# RasPiHAT-SOUND.net
KiCad netlist of a schematic drawn in Altium Designer
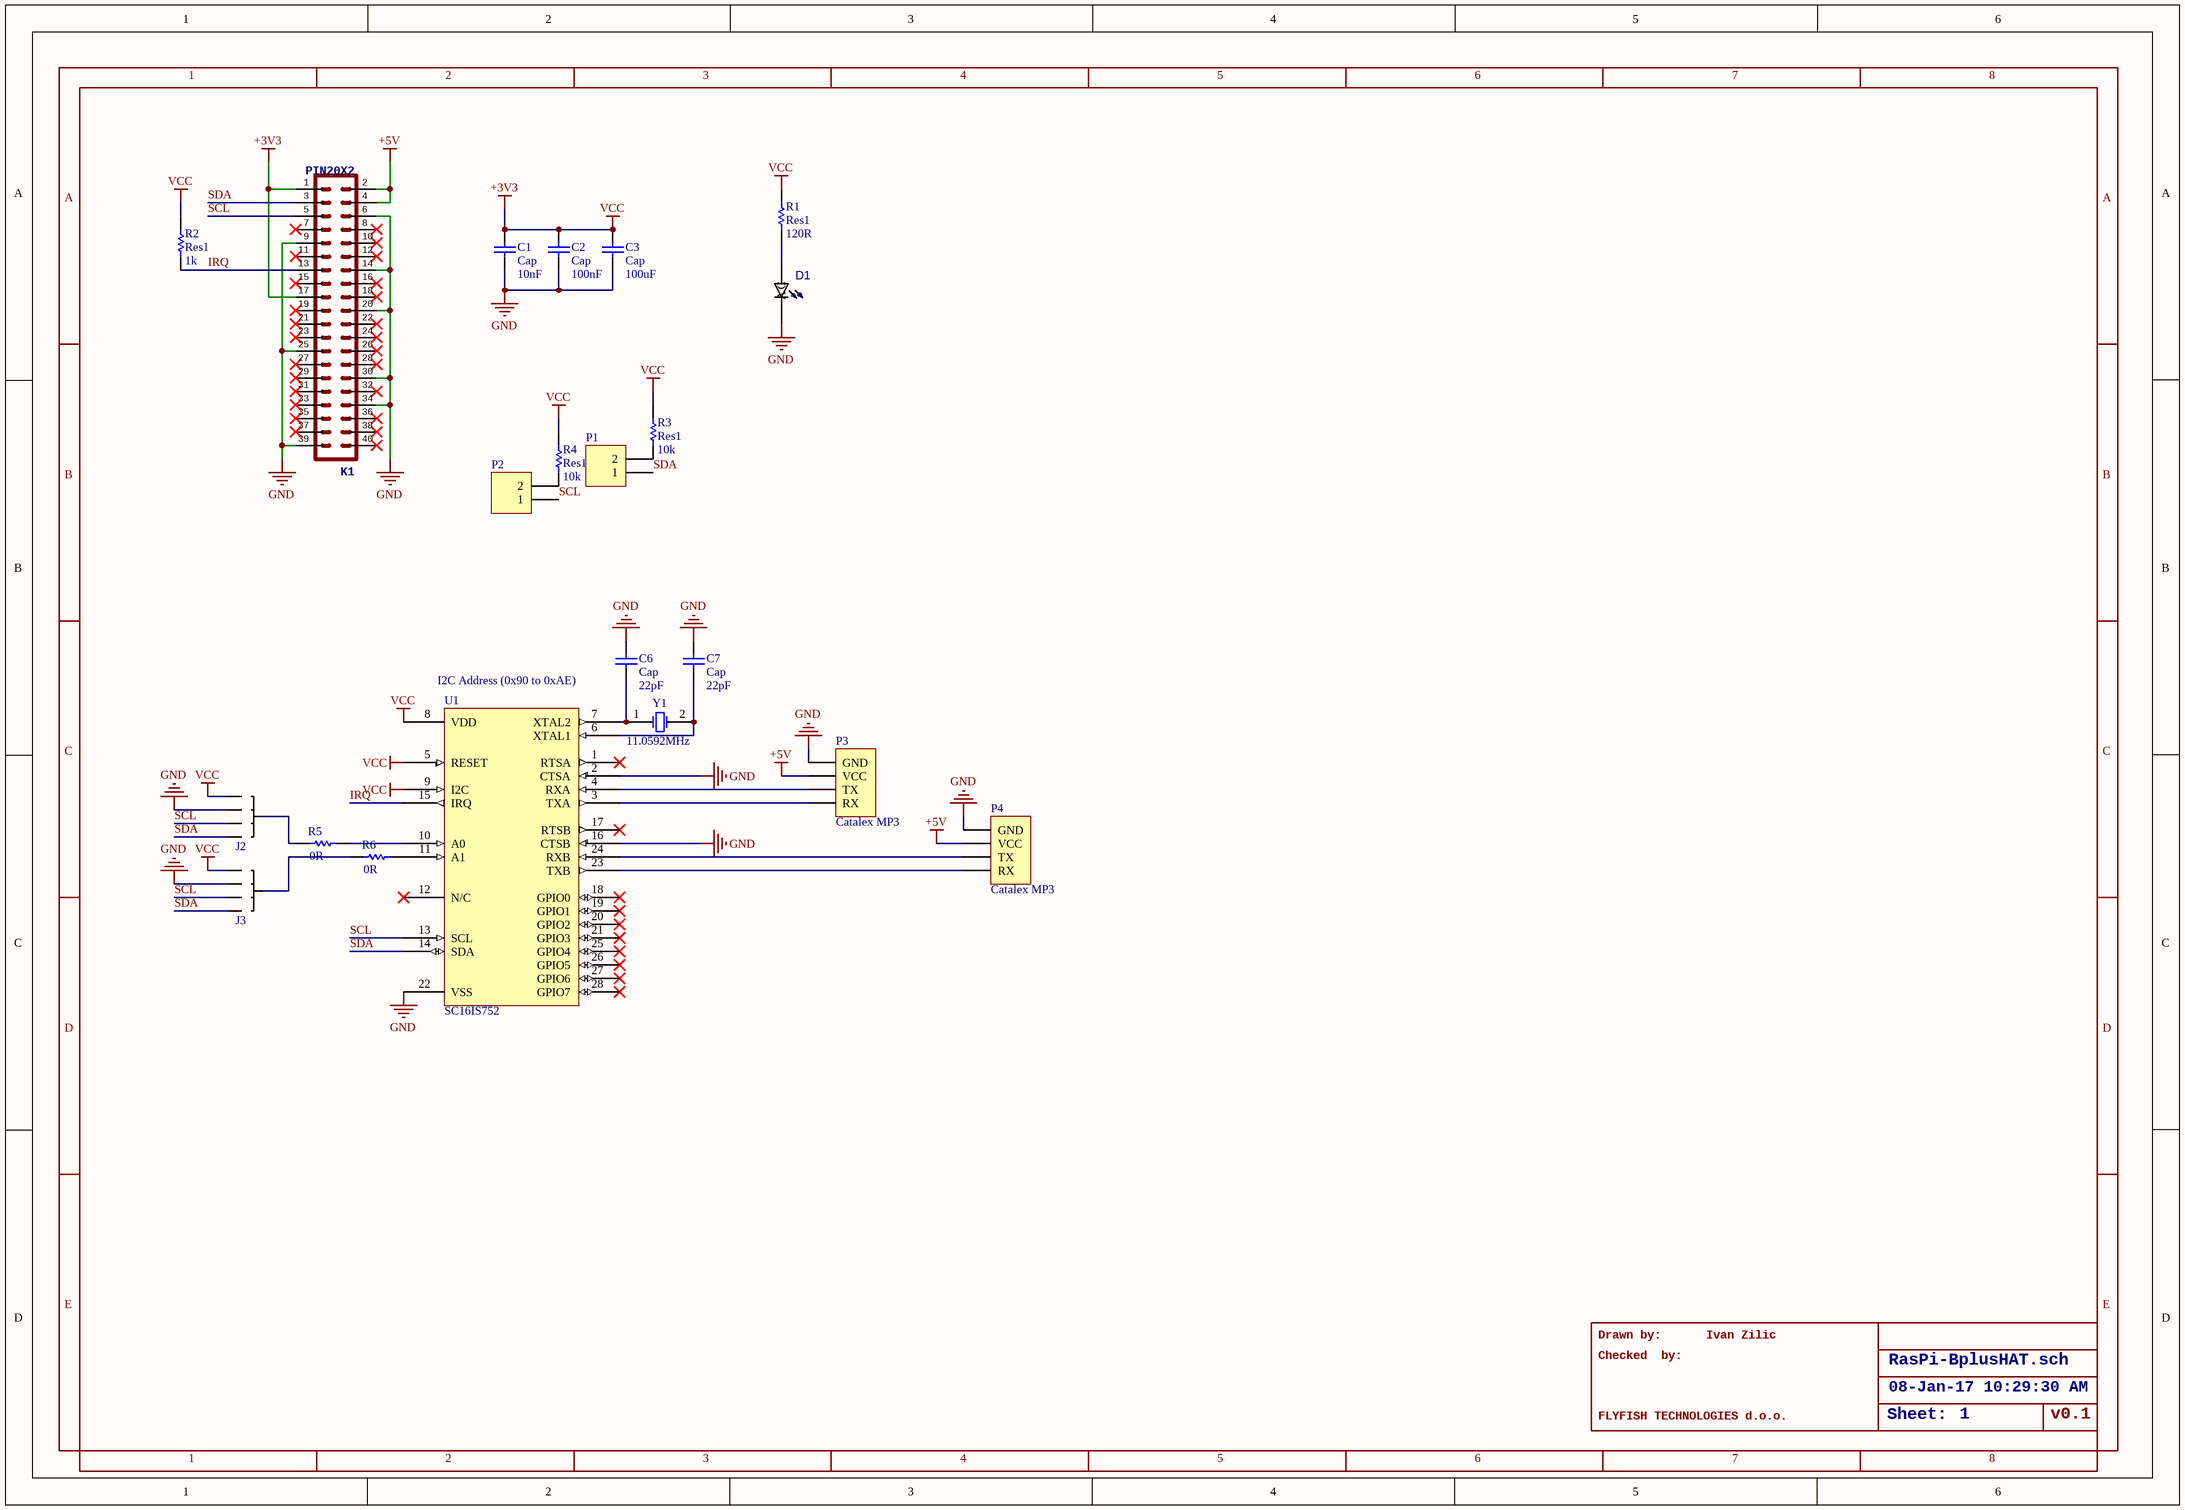
[diagram p0: RasPiHAT-SOUND.SchDoc]

(export (version "E")
  (design (tool "Eeschema 10.0.6"))
  (components
    (comp (ref "C1")
      (value "Cap")
      (footprint "6-0805_N")
      (description "Capacitor")
      (fields (field (name "ALTIUM_VALUE") "10nF") (field (name "PUBLISHER") "Altium Limited"))
      (libsource (lib "Miscellaneous Devices") (part "Cap"))
    )
    (comp (ref "C2")
      (value "Cap")
      (footprint "6-0805_N")
      (description "Capacitor")
      (fields (field (name "ALTIUM_VALUE") "100nF") (field (name "PUBLISHER") "Altium Limited"))
      (libsource (lib "Miscellaneous Devices") (part "Cap"))
    )
    (comp (ref "C3")
      (value "Cap")
      (footprint "6-0805_N")
      (description "Capacitor")
      (fields (field (name "ALTIUM_VALUE") "100uF") (field (name "PUBLISHER") "Altium Limited"))
      (libsource (lib "Miscellaneous Devices") (part "Cap"))
    )
    (comp (ref "C6")
      (value "Cap")
      (footprint "6-0805_N")
      (description "Capacitor")
      (fields (field (name "ALTIUM_VALUE") "22pF") (field (name "PUBLISHER") "Altium Limited"))
      (libsource (lib "Miscellaneous Devices") (part "Cap"))
    )
    (comp (ref "C7")
      (value "Cap")
      (footprint "6-0805_N")
      (description "Capacitor")
      (fields (field (name "ALTIUM_VALUE") "22pF") (field (name "PUBLISHER") "Altium Limited"))
      (libsource (lib "Miscellaneous Devices") (part "Cap"))
    )
    (comp (ref "D1")
      (value "0805_LED")
      (footprint "LEDSC200X125X70-2N_598-8160-107F(Primary)")
      (description "LED, SMD; 0805; Yellow-Green; Water Clear Lens; 40mcd; 570/575nm")
      (fields (field (name "MP") "598-8160-107F") (field (name "MF") "Dialight"))
      (libsource (lib "0805_LED") (part "598-8160-107F"))
    )
    (comp (ref "J2")
      (value "Shortable Link (4 Way)")
      (footprint "ShortableLink(4Way)")
      (libsource (lib "ShortableLink") (part "Shortable Link (4 Way)"))
    )
    (comp (ref "J3")
      (value "Shortable Link (4 Way)")
      (footprint "ShortableLink(4Way)")
      (libsource (lib "ShortableLink") (part "Shortable Link (4 Way)"))
    )
    (comp (ref "K1")
      (value "PIN20X2")
      (footprint "HDR2X20")
      (fields (field (name ">VALUE") "PIN20X2") (field (name ">NAME") "K1"))
      (libsource (lib "FLYFISH") (part "PIN20X2"))
    )
    (comp (ref "P1")
      (value "Header 2")
      (footprint "HDR1X2")
      (description "Header, 2-Pin")
      (fields (field (name "PUBLISHER") "Altium Limited"))
      (libsource (lib "Miscellaneous Connectors") (part "Header 2"))
    )
    (comp (ref "P2")
      (value "Header 2")
      (footprint "HDR1X2")
      (description "Header, 2-Pin")
      (fields (field (name "PUBLISHER") "Altium Limited"))
      (libsource (lib "Miscellaneous Connectors") (part "Header 2"))
    )
    (comp (ref "P3")
      (value "Catalex MP3")
      (footprint "YX5300_UART")
      (description "Header, 4-Pin")
      (fields (field (name "PUBLISHER") "Altium Limited"))
      (libsource (lib "Miscellaneous Connectors") (part "Header 4"))
    )
    (comp (ref "P4")
      (value "Catalex MP3")
      (footprint "YX5300_UART")
      (description "Header, 4-Pin")
      (fields (field (name "PUBLISHER") "Altium Limited"))
      (libsource (lib "Miscellaneous Connectors") (part "Header 4"))
    )
    (comp (ref "R1")
      (value "Res1")
      (footprint "6-0805_N")
      (description "Resistor")
      (fields (field (name "ALTIUM_VALUE") "120R") (field (name "PUBLISHER") "Altium Limited"))
      (libsource (lib "Miscellaneous Devices") (part "Res1"))
    )
    (comp (ref "R2")
      (value "Res1")
      (footprint "6-0805_N")
      (description "Resistor")
      (fields (field (name "ALTIUM_VALUE") "1k") (field (name "PUBLISHER") "Altium Limited"))
      (libsource (lib "Miscellaneous Devices") (part "Res1"))
    )
    (comp (ref "R3")
      (value "Res1")
      (footprint "6-0805_N")
      (description "Resistor")
      (fields (field (name "ALTIUM_VALUE") "10k") (field (name "PUBLISHER") "Altium Limited"))
      (libsource (lib "Miscellaneous Devices") (part "Res1"))
    )
    (comp (ref "R4")
      (value "Res1")
      (footprint "6-0805_N")
      (description "Resistor")
      (fields (field (name "ALTIUM_VALUE") "10k") (field (name "PUBLISHER") "Altium Limited"))
      (libsource (lib "Miscellaneous Devices") (part "Res1"))
    )
    (comp (ref "R5")
      (value "0R")
      (footprint "6-0805_N")
      (description "Resistor")
      (fields (field (name "Comment") "Res1") (field (name "PUBLISHER") "Altium Limited"))
      (libsource (lib "Miscellaneous Devices") (part "Res1"))
    )
    (comp (ref "R6")
      (value "0R")
      (footprint "6-0805_N")
      (description "Resistor")
      (fields (field (name "Comment") "Res1") (field (name "PUBLISHER") "Altium Limited"))
      (libsource (lib "Miscellaneous Devices") (part "Res1"))
    )
    (comp (ref "U1")
      (value "SC16IS752")
      (description "I2C to UART Interface (2 Channels)")
      (libsource (lib "NXP_UART_Interfaces") (part "SC16IS752IPW"))
    )
    (comp (ref "Y1")
      (value "11.0592MHz")
      (footprint "Crystals:SMD Crystal")
      (description "Crystal Oscillator")
      (fields (field (name "PUBLISHER") "Altium Limited"))
      (libsource (lib "Miscellaneous Devices") (part "XTAL"))
    )
  )
  (nets
    (net (code "1") (name "+3V3") (class "Default")
      (node (ref "C1") (pin "2") (pinfunction "2_2") (pintype "passive"))
      (node (ref "C2") (pin "2") (pinfunction "2_2") (pintype "passive"))
      (node (ref "C3") (pin "2") (pinfunction "2_2") (pintype "passive"))
      (node (ref "J2") (pin "5") (pinfunction "5_5") (pintype "passive"))
      (node (ref "J3") (pin "5") (pinfunction "5_5") (pintype "passive"))
      (node (ref "K1") (pin "1") (pinfunction "1_1") (pintype "passive"))
      (node (ref "K1") (pin "17") (pinfunction "17_17") (pintype "passive"))
      (node (ref "R1") (pin "1") (pinfunction "1_1") (pintype "passive"))
      (node (ref "R2") (pin "1") (pinfunction "1_1") (pintype "passive"))
      (node (ref "R3") (pin "1") (pinfunction "1_1") (pintype "passive"))
      (node (ref "R4") (pin "1") (pinfunction "1_1") (pintype "passive"))
      (node (ref "U1") (pin "5") (pinfunction "RESET_5") (pintype "input"))
      (node (ref "U1") (pin "8") (pinfunction "VDD_8") (pintype "passive"))
      (node (ref "U1") (pin "9") (pinfunction "I2C_9") (pintype "input"))
    )
    (net (code "2") (name "+5V") (class "Default")
      (node (ref "K1") (pin "2") (pinfunction "2_2") (pintype "passive"))
      (node (ref "K1") (pin "4") (pinfunction "4_4") (pintype "passive"))
      (node (ref "P3") (pin "2") (pinfunction "VCC_2") (pintype "passive"))
      (node (ref "P4") (pin "2") (pinfunction "VCC_2") (pintype "passive"))
    )
    (net (code "3") (name "/IRQ") (class "Default")
      (node (ref "K1") (pin "13") (pinfunction "13_13") (pintype "passive"))
      (node (ref "R2") (pin "2") (pinfunction "2_2") (pintype "passive"))
      (node (ref "U1") (pin "15") (pinfunction "IRQ_15") (pintype "output"))
    )
    (net (code "4") (name "/SCL") (class "Default")
      (node (ref "J2") (pin "3") (pinfunction "3_3") (pintype "passive"))
      (node (ref "J3") (pin "3") (pinfunction "3_3") (pintype "passive"))
      (node (ref "K1") (pin "5") (pinfunction "5_5") (pintype "passive"))
      (node (ref "P2") (pin "1") (pinfunction "1_1") (pintype "passive"))
      (node (ref "U1") (pin "13") (pinfunction "SCL_13") (pintype "input"))
    )
    (net (code "5") (name "/SDA") (class "Default")
      (node (ref "J2") (pin "2") (pinfunction "2_2") (pintype "passive"))
      (node (ref "J3") (pin "2") (pinfunction "2_2") (pintype "passive"))
      (node (ref "K1") (pin "3") (pinfunction "3_3") (pintype "passive"))
      (node (ref "P1") (pin "1") (pinfunction "1_1") (pintype "passive"))
      (node (ref "U1") (pin "14") (pinfunction "SDA_14") (pintype "bidirectional"))
    )
    (net (code "6") (name "GND") (class "Default")
      (node (ref "C1") (pin "1") (pinfunction "1_1") (pintype "passive"))
      (node (ref "C2") (pin "1") (pinfunction "1_1") (pintype "passive"))
      (node (ref "C3") (pin "1") (pinfunction "1_1") (pintype "passive"))
      (node (ref "C6") (pin "1") (pinfunction "1_1") (pintype "passive"))
      (node (ref "C7") (pin "2") (pinfunction "2_2") (pintype "passive"))
      (node (ref "D1") (pin "C") (pinfunction "C_C") (pintype "passive"))
      (node (ref "J2") (pin "4") (pinfunction "4_4") (pintype "passive"))
      (node (ref "J3") (pin "4") (pinfunction "4_4") (pintype "passive"))
      (node (ref "K1") (pin "14") (pinfunction "14_14") (pintype "passive"))
      (node (ref "K1") (pin "20") (pinfunction "20_20") (pintype "passive"))
      (node (ref "K1") (pin "25") (pinfunction "25_25") (pintype "passive"))
      (node (ref "K1") (pin "30") (pinfunction "30_30") (pintype "passive"))
      (node (ref "K1") (pin "34") (pinfunction "34_34") (pintype "passive"))
      (node (ref "K1") (pin "39") (pinfunction "39_39") (pintype "passive"))
      (node (ref "K1") (pin "6") (pinfunction "6_6") (pintype "passive"))
      (node (ref "K1") (pin "9") (pinfunction "9_9") (pintype "passive"))
      (node (ref "P3") (pin "1") (pinfunction "GND_1") (pintype "passive"))
      (node (ref "P4") (pin "1") (pinfunction "GND_1") (pintype "passive"))
      (node (ref "U1") (pin "16") (pinfunction "CTSB_16") (pintype "input"))
      (node (ref "U1") (pin "2") (pinfunction "CTSA_2") (pintype "input"))
      (node (ref "U1") (pin "22") (pinfunction "VSS_22") (pintype "power_in"))
    )
    (net (code "7") (name "Net-(D1-PadA)") (class "Default")
      (node (ref "D1") (pin "A") (pinfunction "A_A") (pintype "passive"))
      (node (ref "R1") (pin "2") (pinfunction "2_2") (pintype "passive"))
    )
    (net (code "8") (name "Net-(J2-Pad1)") (class "Default")
      (node (ref "J2") (pin "1") (pinfunction "1_1") (pintype "passive"))
      (node (ref "R5") (pin "1") (pinfunction "1_1") (pintype "passive"))
    )
    (net (code "9") (name "Net-(J3-Pad1)") (class "Default")
      (node (ref "J3") (pin "1") (pinfunction "1_1") (pintype "passive"))
      (node (ref "R6") (pin "1") (pinfunction "1_1") (pintype "passive"))
    )
    (net (code "10") (name "Net-(P1-Pad2)") (class "Default")
      (node (ref "P1") (pin "2") (pinfunction "2_2") (pintype "passive"))
      (node (ref "R3") (pin "2") (pinfunction "2_2") (pintype "passive"))
    )
    (net (code "11") (name "Net-(P2-Pad2)") (class "Default")
      (node (ref "P2") (pin "2") (pinfunction "2_2") (pintype "passive"))
      (node (ref "R4") (pin "2") (pinfunction "2_2") (pintype "passive"))
    )
    (net (code "12") (name "Net-(P3-RX)") (class "Default")
      (node (ref "P3") (pin "4") (pinfunction "RX_4") (pintype "passive"))
      (node (ref "U1") (pin "3") (pinfunction "TXA_3") (pintype "output"))
    )
    (net (code "13") (name "Net-(P3-TX)") (class "Default")
      (node (ref "P3") (pin "3") (pinfunction "TX_3") (pintype "passive"))
      (node (ref "U1") (pin "4") (pinfunction "RXA_4") (pintype "input"))
    )
    (net (code "14") (name "Net-(P4-RX)") (class "Default")
      (node (ref "P4") (pin "4") (pinfunction "RX_4") (pintype "passive"))
      (node (ref "U1") (pin "23") (pinfunction "TXB_23") (pintype "output"))
    )
    (net (code "15") (name "Net-(P4-TX)") (class "Default")
      (node (ref "P4") (pin "3") (pinfunction "TX_3") (pintype "passive"))
      (node (ref "U1") (pin "24") (pinfunction "RXB_24") (pintype "input"))
    )
    (net (code "16") (name "Net-(U1-A0)") (class "Default")
      (node (ref "R5") (pin "2") (pinfunction "2_2") (pintype "passive"))
      (node (ref "U1") (pin "10") (pinfunction "A0_10") (pintype "input"))
    )
    (net (code "17") (name "Net-(U1-A1)") (class "Default")
      (node (ref "R6") (pin "2") (pinfunction "2_2") (pintype "passive"))
      (node (ref "U1") (pin "11") (pinfunction "A1_11") (pintype "input"))
    )
    (net (code "18") (name "Net-(U1-XTAL1)") (class "Default")
      (node (ref "C7") (pin "1") (pinfunction "1_1") (pintype "passive"))
      (node (ref "U1") (pin "6") (pinfunction "XTAL1_6") (pintype "input"))
      (node (ref "Y1") (pin "2") (pinfunction "OSC2_2") (pintype "passive"))
    )
    (net (code "19") (name "Net-(U1-XTAL2)") (class "Default")
      (node (ref "C6") (pin "2") (pinfunction "2_2") (pintype "passive"))
      (node (ref "U1") (pin "7") (pinfunction "XTAL2_7") (pintype "output"))
      (node (ref "Y1") (pin "1") (pinfunction "OSC1_1") (pintype "passive"))
    )
    (net (code "20") (name "unconnected-(K1-Pad7)") (class "Default")
      (node (ref "K1") (pin "7") (pinfunction "7_7") (pintype "passive+no_connect"))
    )
    (net (code "21") (name "unconnected-(K1-Pad8)") (class "Default")
      (node (ref "K1") (pin "8") (pinfunction "8_8") (pintype "passive+no_connect"))
    )
    (net (code "22") (name "unconnected-(K1-Pad10)") (class "Default")
      (node (ref "K1") (pin "10") (pinfunction "10_10") (pintype "passive+no_connect"))
    )
    (net (code "23") (name "unconnected-(K1-Pad11)") (class "Default")
      (node (ref "K1") (pin "11") (pinfunction "11_11") (pintype "passive+no_connect"))
    )
    (net (code "24") (name "unconnected-(K1-Pad12)") (class "Default")
      (node (ref "K1") (pin "12") (pinfunction "12_12") (pintype "passive+no_connect"))
    )
    (net (code "25") (name "unconnected-(K1-Pad15)") (class "Default")
      (node (ref "K1") (pin "15") (pinfunction "15_15") (pintype "passive+no_connect"))
    )
    (net (code "26") (name "unconnected-(K1-Pad16)") (class "Default")
      (node (ref "K1") (pin "16") (pinfunction "16_16") (pintype "passive+no_connect"))
    )
    (net (code "27") (name "unconnected-(K1-Pad18)") (class "Default")
      (node (ref "K1") (pin "18") (pinfunction "18_18") (pintype "passive+no_connect"))
    )
    (net (code "28") (name "unconnected-(K1-Pad19)") (class "Default")
      (node (ref "K1") (pin "19") (pinfunction "19_19") (pintype "passive+no_connect"))
    )
    (net (code "29") (name "unconnected-(K1-Pad21)") (class "Default")
      (node (ref "K1") (pin "21") (pinfunction "21_21") (pintype "passive+no_connect"))
    )
    (net (code "30") (name "unconnected-(K1-Pad22)") (class "Default")
      (node (ref "K1") (pin "22") (pinfunction "22_22") (pintype "passive+no_connect"))
    )
    (net (code "31") (name "unconnected-(K1-Pad23)") (class "Default")
      (node (ref "K1") (pin "23") (pinfunction "23_23") (pintype "passive+no_connect"))
    )
    (net (code "32") (name "unconnected-(K1-Pad24)") (class "Default")
      (node (ref "K1") (pin "24") (pinfunction "24_24") (pintype "passive+no_connect"))
    )
    (net (code "33") (name "unconnected-(K1-Pad26)") (class "Default")
      (node (ref "K1") (pin "26") (pinfunction "26_26") (pintype "passive+no_connect"))
    )
    (net (code "34") (name "unconnected-(K1-Pad27)") (class "Default")
      (node (ref "K1") (pin "27") (pinfunction "27_27") (pintype "passive+no_connect"))
    )
    (net (code "35") (name "unconnected-(K1-Pad28)") (class "Default")
      (node (ref "K1") (pin "28") (pinfunction "28_28") (pintype "passive+no_connect"))
    )
    (net (code "36") (name "unconnected-(K1-Pad29)") (class "Default")
      (node (ref "K1") (pin "29") (pinfunction "29_29") (pintype "passive+no_connect"))
    )
    (net (code "37") (name "unconnected-(K1-Pad31)") (class "Default")
      (node (ref "K1") (pin "31") (pinfunction "31_31") (pintype "passive+no_connect"))
    )
    (net (code "38") (name "unconnected-(K1-Pad32)") (class "Default")
      (node (ref "K1") (pin "32") (pinfunction "32_32") (pintype "passive+no_connect"))
    )
    (net (code "39") (name "unconnected-(K1-Pad33)") (class "Default")
      (node (ref "K1") (pin "33") (pinfunction "33_33") (pintype "passive+no_connect"))
    )
    (net (code "40") (name "unconnected-(K1-Pad35)") (class "Default")
      (node (ref "K1") (pin "35") (pinfunction "35_35") (pintype "passive+no_connect"))
    )
    (net (code "41") (name "unconnected-(K1-Pad36)") (class "Default")
      (node (ref "K1") (pin "36") (pinfunction "36_36") (pintype "passive+no_connect"))
    )
    (net (code "42") (name "unconnected-(K1-Pad37)") (class "Default")
      (node (ref "K1") (pin "37") (pinfunction "37_37") (pintype "passive+no_connect"))
    )
    (net (code "43") (name "unconnected-(K1-Pad38)") (class "Default")
      (node (ref "K1") (pin "38") (pinfunction "38_38") (pintype "passive+no_connect"))
    )
    (net (code "44") (name "unconnected-(K1-Pad40)") (class "Default")
      (node (ref "K1") (pin "40") (pinfunction "40_40") (pintype "passive+no_connect"))
    )
    (net (code "45") (name "unconnected-(U1-GPIO0-Pad18)") (class "Default")
      (node (ref "U1") (pin "18") (pinfunction "GPIO0_18") (pintype "bidirectional+no_connect"))
    )
    (net (code "46") (name "unconnected-(U1-GPIO1-Pad19)") (class "Default")
      (node (ref "U1") (pin "19") (pinfunction "GPIO1_19") (pintype "bidirectional+no_connect"))
    )
    (net (code "47") (name "unconnected-(U1-GPIO2-Pad20)") (class "Default")
      (node (ref "U1") (pin "20") (pinfunction "GPIO2_20") (pintype "bidirectional+no_connect"))
    )
    (net (code "48") (name "unconnected-(U1-GPIO3-Pad21)") (class "Default")
      (node (ref "U1") (pin "21") (pinfunction "GPIO3_21") (pintype "bidirectional+no_connect"))
    )
    (net (code "49") (name "unconnected-(U1-GPIO4-Pad25)") (class "Default")
      (node (ref "U1") (pin "25") (pinfunction "GPIO4_25") (pintype "bidirectional+no_connect"))
    )
    (net (code "50") (name "unconnected-(U1-GPIO5-Pad26)") (class "Default")
      (node (ref "U1") (pin "26") (pinfunction "GPIO5_26") (pintype "bidirectional+no_connect"))
    )
    (net (code "51") (name "unconnected-(U1-GPIO6-Pad27)") (class "Default")
      (node (ref "U1") (pin "27") (pinfunction "GPIO6_27") (pintype "bidirectional+no_connect"))
    )
    (net (code "52") (name "unconnected-(U1-GPIO7-Pad28)") (class "Default")
      (node (ref "U1") (pin "28") (pinfunction "GPIO7_28") (pintype "bidirectional+no_connect"))
    )
    (net (code "53") (name "unconnected-(U1-N{slash}C-Pad12)") (class "Default")
      (node (ref "U1") (pin "12") (pinfunction "N/C_12") (pintype "passive+no_connect"))
    )
    (net (code "54") (name "unconnected-(U1-RTSA-Pad1)") (class "Default")
      (node (ref "U1") (pin "1") (pinfunction "RTSA_1") (pintype "output+no_connect"))
    )
    (net (code "55") (name "unconnected-(U1-RTSB-Pad17)") (class "Default")
      (node (ref "U1") (pin "17") (pinfunction "RTSB_17") (pintype "output+no_connect"))
    )
  )
)
